# fact-atmega8.net
KiCad netlist of a schematic drawn in EAGLE
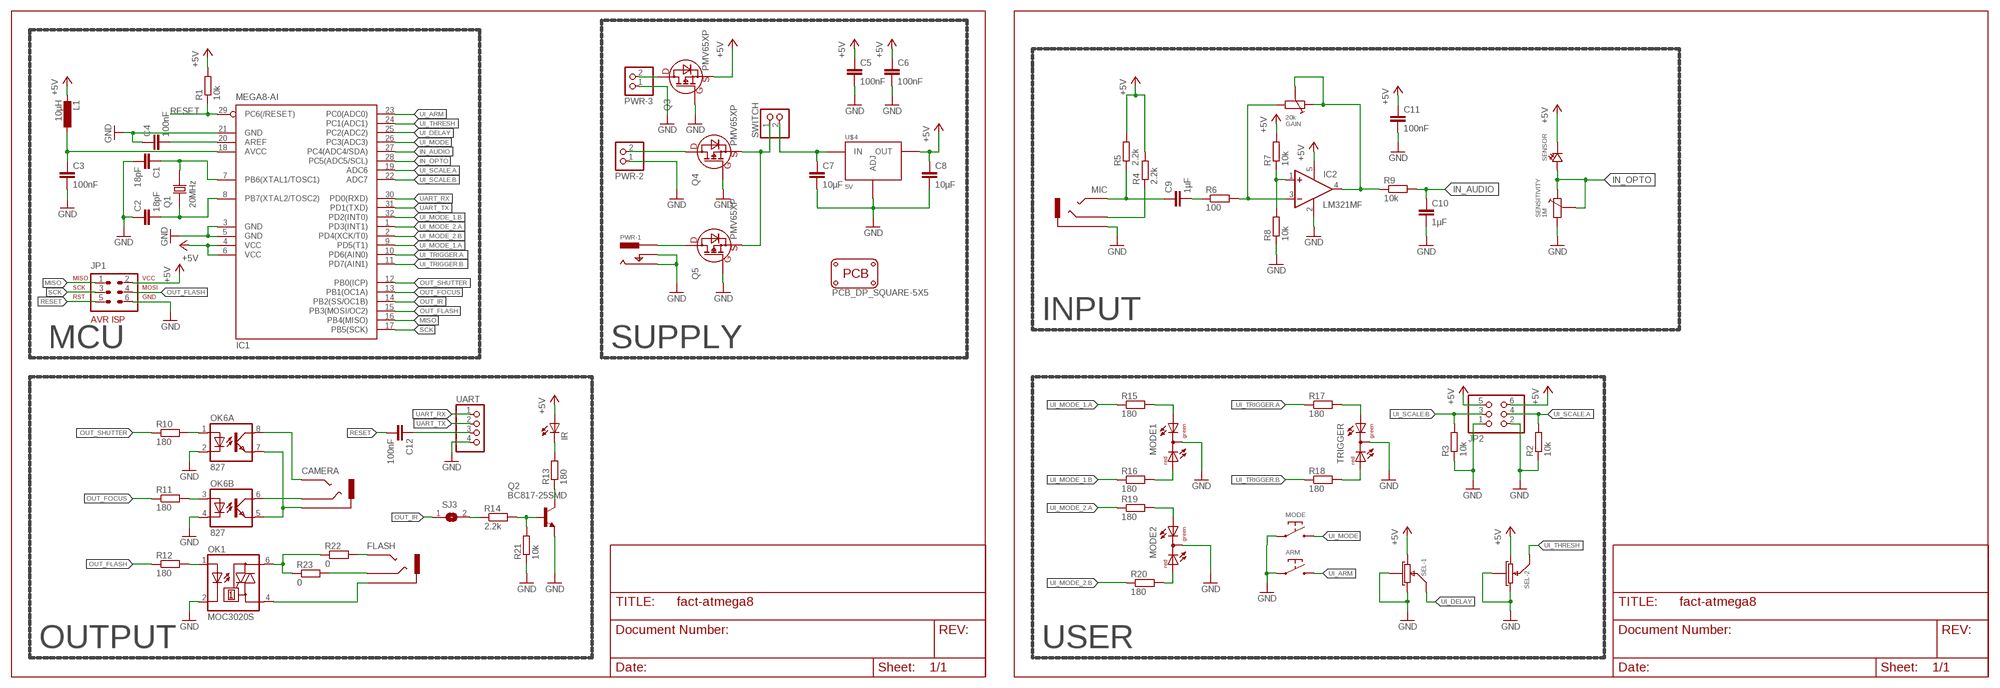
[diagram p0: schematic, sheet 1]

(export (version "E")
  (design (tool "Eeschema 10.0.6"))
  (components
    (comp (ref "ARM")
      (value "SWITCH-DEFAULT_OFF")
      (footprint "eagle-import:SWITCH-GENERIC-4_PIN")
      (libsource (lib "eagle-import") (part "SWITCH-DEFAULT_OFF"))
    )
    (comp (ref "C1")
      (value "18pF")
      (footprint "eagle-import:C0603")
      (libsource (lib "eagle-import") (part "C-EUC0603"))
    )
    (comp (ref "C2")
      (value "18pF")
      (footprint "eagle-import:C0603")
      (libsource (lib "eagle-import") (part "C-EUC0603"))
    )
    (comp (ref "C3")
      (value "100nF")
      (footprint "eagle-import:C0603")
      (libsource (lib "eagle-import") (part "C-EUC0603"))
    )
    (comp (ref "C4")
      (value "100nF")
      (footprint "eagle-import:C0603")
      (libsource (lib "eagle-import") (part "C-EUC0603"))
    )
    (comp (ref "C5")
      (value "100nF")
      (footprint "eagle-import:C0603")
      (libsource (lib "eagle-import") (part "C-EUC0603"))
    )
    (comp (ref "C6")
      (value "100nF")
      (footprint "eagle-import:C0603")
      (libsource (lib "eagle-import") (part "C-EUC0603"))
    )
    (comp (ref "C7")
      (value "10µF")
      (footprint "eagle-import:C0603")
      (libsource (lib "eagle-import") (part "C-EUC0603"))
    )
    (comp (ref "C8")
      (value "10µF")
      (footprint "eagle-import:C0603")
      (libsource (lib "eagle-import") (part "C-EUC0603"))
    )
    (comp (ref "C9")
      (value "1µF")
      (footprint "eagle-import:C0603")
      (libsource (lib "eagle-import") (part "C-EUC0603"))
    )
    (comp (ref "C10")
      (value "1µF")
      (footprint "eagle-import:C0603")
      (libsource (lib "eagle-import") (part "C-EUC0603"))
    )
    (comp (ref "C11")
      (value "100nF")
      (footprint "eagle-import:C0603")
      (libsource (lib "eagle-import") (part "C-EUC0603"))
    )
    (comp (ref "C12")
      (value "100nF")
      (footprint "eagle-import:C0603")
      (libsource (lib "eagle-import") (part "C-EUC0603"))
    )
    (comp (ref "CAMERA")
      (value "AUDIO-STEREO2MM5")
      (footprint "eagle-import:AUDIO-STEREO-2MM5-SJ1-2503A")
      (libsource (lib "eagle-import") (part "AUDIO-STEREO2MM5"))
    )
    (comp (ref "FLASH")
      (value "AUDIO-STEREOCONRAD")
      (footprint "eagle-import:AUDIO-STEREO-CONRAD-KB3-3_PIN")
      (libsource (lib "eagle-import") (part "AUDIO-STEREOCONRAD"))
    )
    (comp (ref "GAIN")
      (value "20k")
      (footprint "eagle-import:TRIM-POT-CA6-VS5")
      (libsource (lib "eagle-import") (part "TRIM-POT"))
    )
    (comp (ref "IC1")
      (value "MEGA8-AI")
      (footprint "eagle-import:TQFP32-08")
      (fields (field (name "MPN") "ATMEGA8-16AU"))
      (libsource (lib "eagle-import") (part "MEGA8-AI"))
    )
    (comp (ref "IC2")
      (value "LM321MF")
      (footprint "eagle-import:SOT23-5")
      (libsource (lib "eagle-import") (part "LM321?MF"))
    )
    (comp (ref "IR")
      (value "LED5MM")
      (footprint "eagle-import:LED5MM")
      (libsource (lib "eagle-import") (part "LED5MM"))
    )
    (comp (ref "JP1")
      (value "AVR-ISP-6VERT")
      (footprint "eagle-import:AVR-ISP-6")
      (libsource (lib "eagle-import") (part "AVR-ISP-6VERT"))
    )
    (comp (ref "JP2")
      (value "PINHD-2X3")
      (footprint "eagle-import:2X03")
      (libsource (lib "eagle-import") (part "PINHD-2X3"))
    )
    (comp (ref "L1")
      (value "10µH")
      (footprint "eagle-import:R0805")
      (libsource (lib "eagle-import") (part "INDUCTOR0805"))
    )
    (comp (ref "MIC")
      (value "AUDIO-STEREOCONRAD-KB3")
      (footprint "eagle-import:AUDIO-STEREO-CONRAD-KB3-3_PIN")
      (libsource (lib "eagle-import") (part "AUDIO-STEREOCONRAD-KB3"))
    )
    (comp (ref "MODE")
      (value "SWITCH-DEFAULT_OFF")
      (footprint "eagle-import:SWITCH-GENERIC-4_PIN")
      (libsource (lib "eagle-import") (part "SWITCH-DEFAULT_OFF"))
    )
    (comp (ref "MODE1")
      (value "DUOLED-RG-C")
      (footprint "eagle-import:DUOLED-C-5MM")
      (libsource (lib "eagle-import") (part "DUOLED-RG-C"))
    )
    (comp (ref "MODE2")
      (value "DUOLED-RG-C")
      (footprint "eagle-import:DUOLED-C-5MM")
      (libsource (lib "eagle-import") (part "DUOLED-RG-C"))
    )
    (comp (ref "OK1")
      (value "MOC3020S")
      (footprint "eagle-import:DIL6-SMD")
      (fields (field (name "MF") "FAIRCHILD SEMICONDUCTOR") (field (name "MPN") "MOC3032S-M"))
      (libsource (lib "eagle-import") (part "MOC30S32"))
    )
    (comp (ref "OK6")
      (value "827")
      (footprint "eagle-import:SMD08")
      (libsource (lib "eagle-import") (part "OPTOCOUPLER-PC827SMD"))
    )
    (comp (ref "PCB1")
      (value "PCB_DP_SQUARE-5X5")
      (footprint "eagle-import:DP5050_V1")
      (libsource (lib "eagle-import") (part "PCB_DP_SQUARE-5X5"))
    )
    (comp (ref "PWR-1")
      (value "POWER-BARREL_JACKPJ-102A")
      (footprint "eagle-import:POWER-BARREL-2MM1-PJ_102A")
      (libsource (lib "eagle-import") (part "POWER-BARREL_JACKPJ-102A"))
    )
    (comp (ref "PWR-2")
      (value "PINHD-1X2")
      (footprint "eagle-import:1X02")
      (libsource (lib "eagle-import") (part "PINHD-1X2"))
    )
    (comp (ref "PWR-3")
      (value "PINHD-1X2")
      (footprint "eagle-import:1X02")
      (libsource (lib "eagle-import") (part "PINHD-1X2"))
    )
    (comp (ref "Q1")
      (value "20MHz")
      (footprint "eagle-import:CRYSTAL-SMD-5MM_X_3.2MM")
      (libsource (lib "eagle-import") (part "CRYSTAL"))
    )
    (comp (ref "Q2")
      (value "BC817-25SMD")
      (footprint "eagle-import:SOT23-BEC")
      (libsource (lib "eagle-import") (part "BC817SMD-25"))
    )
    (comp (ref "Q3")
      (value "PMV65XP")
      (footprint "eagle-import:SOT23")
      (libsource (lib "eagle-import") (part "FET-P"))
    )
    (comp (ref "Q4")
      (value "PMV65XP")
      (footprint "eagle-import:SOT23")
      (libsource (lib "eagle-import") (part "FET-P"))
    )
    (comp (ref "Q5")
      (value "PMV65XP")
      (footprint "eagle-import:SOT23")
      (libsource (lib "eagle-import") (part "FET-P"))
    )
    (comp (ref "R1")
      (value "10k")
      (footprint "eagle-import:R0603")
      (libsource (lib "eagle-import") (part "R-EU_R0603"))
    )
    (comp (ref "R2")
      (value "10k")
      (footprint "eagle-import:R0603")
      (libsource (lib "eagle-import") (part "R-EU_R0603"))
    )
    (comp (ref "R3")
      (value "10k")
      (footprint "eagle-import:R0603")
      (libsource (lib "eagle-import") (part "R-EU_R0603"))
    )
    (comp (ref "R4")
      (value "2.2k")
      (footprint "eagle-import:R0603")
      (libsource (lib "eagle-import") (part "R-EU_R0603"))
    )
    (comp (ref "R5")
      (value "2.2k")
      (footprint "eagle-import:R0603")
      (libsource (lib "eagle-import") (part "R-EU_R0603"))
    )
    (comp (ref "R6")
      (value "100")
      (footprint "eagle-import:R0603")
      (libsource (lib "eagle-import") (part "R-EU_R0603"))
    )
    (comp (ref "R7")
      (value "10k")
      (footprint "eagle-import:R0603")
      (libsource (lib "eagle-import") (part "R-EU_R0603"))
    )
    (comp (ref "R8")
      (value "10k")
      (footprint "eagle-import:R0603")
      (libsource (lib "eagle-import") (part "R-EU_R0603"))
    )
    (comp (ref "R9")
      (value "10k")
      (footprint "eagle-import:R0603")
      (libsource (lib "eagle-import") (part "R-EU_R0603"))
    )
    (comp (ref "R10")
      (value "180")
      (footprint "eagle-import:R0603")
      (libsource (lib "eagle-import") (part "R-EU_R0603"))
    )
    (comp (ref "R11")
      (value "180")
      (footprint "eagle-import:R0603")
      (libsource (lib "eagle-import") (part "R-EU_R0603"))
    )
    (comp (ref "R12")
      (value "180")
      (footprint "eagle-import:R0603")
      (libsource (lib "eagle-import") (part "R-EU_R0603"))
    )
    (comp (ref "R13")
      (value "180")
      (footprint "eagle-import:R0603")
      (libsource (lib "eagle-import") (part "R-EU_R0603"))
    )
    (comp (ref "R14")
      (value "2.2k")
      (footprint "eagle-import:R0603")
      (libsource (lib "eagle-import") (part "R-EU_R0603"))
    )
    (comp (ref "R15")
      (value "180")
      (footprint "eagle-import:R0603")
      (libsource (lib "eagle-import") (part "R-EU_R0603"))
    )
    (comp (ref "R16")
      (value "180")
      (footprint "eagle-import:R0603")
      (libsource (lib "eagle-import") (part "R-EU_R0603"))
    )
    (comp (ref "R17")
      (value "180")
      (footprint "eagle-import:R0603")
      (libsource (lib "eagle-import") (part "R-EU_R0603"))
    )
    (comp (ref "R18")
      (value "180")
      (footprint "eagle-import:R0603")
      (libsource (lib "eagle-import") (part "R-EU_R0603"))
    )
    (comp (ref "R19")
      (value "180")
      (footprint "eagle-import:R0603")
      (libsource (lib "eagle-import") (part "R-EU_R0603"))
    )
    (comp (ref "R20")
      (value "180")
      (footprint "eagle-import:R0603")
      (libsource (lib "eagle-import") (part "R-EU_R0603"))
    )
    (comp (ref "R21")
      (value "10k")
      (footprint "eagle-import:R0603")
      (libsource (lib "eagle-import") (part "R-EU_R0603"))
    )
    (comp (ref "R22")
      (value "0")
      (footprint "eagle-import:R1206")
      (libsource (lib "eagle-import") (part "rcl_R-EU_R1206"))
    )
    (comp (ref "R23")
      (value "0")
      (footprint "eagle-import:R1206")
      (libsource (lib "eagle-import") (part "rcl_R-EU_R1206"))
    )
    (comp (ref "SEL")
      (value "DUAL-POT")
      (footprint "eagle-import:POT-DUAL-P090")
      (libsource (lib "eagle-import") (part "DUAL-POT"))
    )
    (comp (ref "SENSITIVITY")
      (value "1M")
      (footprint "eagle-import:TRIM-POT-CA6-VS5")
      (libsource (lib "eagle-import") (part "TRIM-POT"))
    )
    (comp (ref "SENSOR")
      (value "PHOTODIODE")
      (footprint "eagle-import:LED-5MM")
      (libsource (lib "eagle-import") (part "PHOTODIODE"))
    )
    (comp (ref "SJ3") (value "SJ") (footprint "eagle-import:SJ") (libsource (lib "eagle-import") (part "SJ")))
    (comp (ref "SWITCH")
      (value "PINHD-1X2")
      (footprint "eagle-import:1X02")
      (libsource (lib "eagle-import") (part "PINHD-1X2"))
    )
    (comp (ref "TRIGGER")
      (value "DUOLED-RG-C")
      (footprint "eagle-import:DUOLED-C-5MM")
      (libsource (lib "eagle-import") (part "DUOLED-RG-C"))
    )
    (comp (ref "U$4")
      (value "5V")
      (footprint "eagle-import:SOT223")
      (libsource (lib "eagle-import") (part "REGULATOR-TLV1117SOT223"))
    )
    (comp (ref "UART")
      (value "PINHD-1X4")
      (footprint "eagle-import:1X04")
      (libsource (lib "eagle-import") (part "PINHD-1X4"))
    )
  )
  (nets
    (net (code "1") (name "+5V") (class "Default")
      (node (ref "C11") (pin "1") (pinfunction "1_1") (pintype "passive"))
      (node (ref "C5") (pin "1") (pinfunction "1_1") (pintype "passive"))
      (node (ref "C6") (pin "1") (pinfunction "1_1") (pintype "passive"))
      (node (ref "C8") (pin "1") (pinfunction "1_1") (pintype "passive"))
      (node (ref "IC1") (pin "4") (pinfunction "VCC_4") (pintype "power_in"))
      (node (ref "IC1") (pin "6") (pinfunction "VCC_6") (pintype "power_in"))
      (node (ref "IC2") (pin "5") (pinfunction "V+_5") (pintype "power_in"))
      (node (ref "IR") (pin "A") (pinfunction "A_A") (pintype "passive"))
      (node (ref "JP1") (pin "2") (pinfunction "2_2") (pintype "passive"))
      (node (ref "JP2") (pin "5") (pinfunction "5_5") (pintype "passive"))
      (node (ref "JP2") (pin "6") (pinfunction "6_6") (pintype "passive"))
      (node (ref "L1") (pin "2") (pinfunction "2_2") (pintype "passive"))
      (node (ref "Q3") (pin "P$2") (pinfunction "SOURCE_P$2") (pintype "bidirectional"))
      (node (ref "R1") (pin "2") (pinfunction "2_2") (pintype "passive"))
      (node (ref "R4") (pin "2") (pinfunction "2_2") (pintype "passive"))
      (node (ref "R5") (pin "2") (pinfunction "2_2") (pintype "passive"))
      (node (ref "R7") (pin "2") (pinfunction "2_2") (pintype "passive"))
      (node (ref "SEL") (pin "P1-3") (pinfunction "B_P1-3") (pintype "bidirectional"))
      (node (ref "SEL") (pin "P2-1") (pinfunction "A_P2-1") (pintype "bidirectional"))
      (node (ref "SENSOR") (pin "K") (pinfunction "C_K") (pintype "bidirectional"))
      (node (ref "U$4") (pin "2") (pinfunction "OUT_2") (pintype "bidirectional"))
    )
    (net (code "2") (name "GND") (class "Default")
      (node (ref "ARM") (pin "P$1") (pinfunction "P$1_P$1") (pintype "bidirectional"))
      (node (ref "ARM") (pin "P$2") (pinfunction "P$1_P$2") (pintype "bidirectional"))
      (node (ref "C1") (pin "2") (pinfunction "2_2") (pintype "passive"))
      (node (ref "C10") (pin "2") (pinfunction "2_2") (pintype "passive"))
      (node (ref "C11") (pin "2") (pinfunction "2_2") (pintype "passive"))
      (node (ref "C2") (pin "1") (pinfunction "1_1") (pintype "passive"))
      (node (ref "C3") (pin "2") (pinfunction "2_2") (pintype "passive"))
      (node (ref "C4") (pin "1") (pinfunction "1_1") (pintype "passive"))
      (node (ref "C5") (pin "2") (pinfunction "2_2") (pintype "passive"))
      (node (ref "C6") (pin "2") (pinfunction "2_2") (pintype "passive"))
      (node (ref "C7") (pin "2") (pinfunction "2_2") (pintype "passive"))
      (node (ref "C8") (pin "2") (pinfunction "2_2") (pintype "passive"))
      (node (ref "IC1") (pin "21") (pinfunction "GND_21") (pintype "power_in"))
      (node (ref "IC1") (pin "3") (pinfunction "GND_3") (pintype "power_in"))
      (node (ref "IC1") (pin "5") (pinfunction "GND_5") (pintype "power_in"))
      (node (ref "IC2") (pin "2") (pinfunction "V-_2") (pintype "power_in"))
      (node (ref "JP1") (pin "6") (pinfunction "6_6") (pintype "passive"))
      (node (ref "JP2") (pin "1") (pinfunction "1_1") (pintype "passive"))
      (node (ref "JP2") (pin "2") (pinfunction "2_2") (pintype "passive"))
      (node (ref "MIC") (pin "2.1") (pinfunction "SLEEVE_2.1") (pintype "passive"))
      (node (ref "MIC") (pin "2.2") (pinfunction "SLEEVE_2.2") (pintype "passive"))
      (node (ref "MODE") (pin "P$1") (pinfunction "P$1_P$1") (pintype "bidirectional"))
      (node (ref "MODE") (pin "P$2") (pinfunction "P$1_P$2") (pintype "bidirectional"))
      (node (ref "MODE1") (pin "C") (pinfunction "C_C") (pintype "passive"))
      (node (ref "MODE2") (pin "C") (pinfunction "C_C") (pintype "passive"))
      (node (ref "OK1") (pin "2") (pinfunction "C_2") (pintype "passive"))
      (node (ref "OK6") (pin "2") (pinfunction "C_2") (pintype "passive"))
      (node (ref "OK6") (pin "4") (pinfunction "C_4") (pintype "passive"))
      (node (ref "PWR-1") (pin "P$2") (pinfunction "OUTER_P$2") (pintype "bidirectional"))
      (node (ref "PWR-1") (pin "P$3") (pinfunction "SWITCH_P$3") (pintype "bidirectional"))
      (node (ref "PWR-2") (pin "1") (pinfunction "1_1") (pintype "passive"))
      (node (ref "PWR-3") (pin "1") (pinfunction "1_1") (pintype "passive"))
      (node (ref "Q2") (pin "E") (pinfunction "E_E") (pintype "passive"))
      (node (ref "Q3") (pin "P$1") (pinfunction "GATE_P$1") (pintype "bidirectional"))
      (node (ref "Q4") (pin "P$1") (pinfunction "GATE_P$1") (pintype "bidirectional"))
      (node (ref "Q5") (pin "P$1") (pinfunction "GATE_P$1") (pintype "bidirectional"))
      (node (ref "R2") (pin "1") (pinfunction "1_1") (pintype "passive"))
      (node (ref "R21") (pin "1") (pinfunction "1_1") (pintype "passive"))
      (node (ref "R3") (pin "1") (pinfunction "1_1") (pintype "passive"))
      (node (ref "R8") (pin "1") (pinfunction "1_1") (pintype "passive"))
      (node (ref "SEL") (pin "CENTER") (pinfunction "SHIELD_CENTER") (pintype "bidirectional"))
      (node (ref "SEL") (pin "G1-S") (pinfunction "SHIELD_G1-S") (pintype "bidirectional"))
      (node (ref "SEL") (pin "G2-S") (pinfunction "SHIELD_G2-S") (pintype "bidirectional"))
      (node (ref "SEL") (pin "P1-1") (pinfunction "A_P1-1") (pintype "bidirectional"))
      (node (ref "SEL") (pin "P2-3") (pinfunction "B_P2-3") (pintype "bidirectional"))
      (node (ref "SENSITIVITY") (pin "P$2") (pinfunction "P$2_P$2") (pintype "bidirectional"))
      (node (ref "TRIGGER") (pin "C") (pinfunction "C_C") (pintype "passive"))
      (node (ref "U$4") (pin "1") (pinfunction "ADJ_1") (pintype "bidirectional"))
      (node (ref "U$4") (pin "4") (pinfunction "ADJ_4") (pintype "bidirectional"))
      (node (ref "UART") (pin "4") (pinfunction "4_4") (pintype "passive"))
    )
    (net (code "3") (name "IN_AUDIO") (class "Default")
      (node (ref "C10") (pin "1") (pinfunction "1_1") (pintype "passive"))
      (node (ref "IC1") (pin "27") (pinfunction "PC4(ADC4/SDA)_27") (pintype "bidirectional"))
      (node (ref "R9") (pin "2") (pinfunction "2_2") (pintype "passive"))
    )
    (net (code "4") (name "IN_OPTO") (class "Default")
      (node (ref "IC1") (pin "28") (pinfunction "PC5(ADC5/SCL)_28") (pintype "bidirectional"))
      (node (ref "SENSITIVITY") (pin "CENTER") (pinfunction "CENTER_CENTER") (pintype "bidirectional"))
      (node (ref "SENSITIVITY") (pin "P$1") (pinfunction "P$1_P$1") (pintype "bidirectional"))
      (node (ref "SENSOR") (pin "A") (pinfunction "A_A") (pintype "bidirectional"))
    )
    (net (code "5") (name "MISO") (class "Default")
      (node (ref "IC1") (pin "16") (pinfunction "PB4(MISO)_16") (pintype "bidirectional"))
      (node (ref "JP1") (pin "1") (pinfunction "1_1") (pintype "passive"))
    )
    (net (code "6") (name "Net-(C9-Pad2)") (class "Default")
      (node (ref "C9") (pin "2") (pinfunction "2_2") (pintype "passive"))
      (node (ref "R6") (pin "1") (pinfunction "1_1") (pintype "passive"))
    )
    (net (code "7") (name "Net-(C12-Pad1)") (class "Default")
      (node (ref "C12") (pin "1") (pinfunction "1_1") (pintype "passive"))
      (node (ref "UART") (pin "3") (pinfunction "3_3") (pintype "passive"))
    )
    (net (code "8") (name "Net-(CAMERA-RING)") (class "Default")
      (node (ref "CAMERA") (pin "P$4") (pinfunction "RING_P$4") (pintype "passive"))
      (node (ref "OK6") (pin "6") (pinfunction "COL_6") (pintype "passive"))
    )
    (net (code "9") (name "Net-(CAMERA-SLEEVE)") (class "Default")
      (node (ref "CAMERA") (pin "P$1") (pinfunction "SLEEVE_P$1") (pintype "passive"))
      (node (ref "OK6") (pin "5") (pinfunction "EMIT_5") (pintype "passive"))
      (node (ref "OK6") (pin "7") (pinfunction "EMIT_7") (pintype "passive"))
    )
    (net (code "10") (name "Net-(FLASH-RING-Pad2.1)") (class "Default")
      (node (ref "FLASH") (pin "2.1") (pinfunction "RING_2.1") (pintype "passive"))
      (node (ref "FLASH") (pin "2.2") (pinfunction "RING_2.2") (pintype "passive"))
      (node (ref "R23") (pin "2") (pinfunction "2_2") (pintype "passive"))
    )
    (net (code "11") (name "Net-(FLASH-SLEEVE)") (class "Default")
      (node (ref "FLASH") (pin "1") (pinfunction "SLEEVE_1") (pintype "passive"))
      (node (ref "OK1") (pin "4") (pinfunction "A1_4") (pintype "passive"))
    )
    (net (code "12") (name "Net-(FLASH-TIP)") (class "Default")
      (node (ref "FLASH") (pin "3") (pinfunction "TIP_3") (pintype "passive"))
      (node (ref "R22") (pin "2") (pinfunction "2_2") (pintype "passive"))
    )
    (net (code "13") (name "Net-(IC1-AREF)") (class "Default")
      (node (ref "C4") (pin "2") (pinfunction "2_2") (pintype "passive"))
      (node (ref "IC1") (pin "20") (pinfunction "AREF_20") (pintype "passive"))
    )
    (net (code "14") (name "Net-(IC1-AVCC)") (class "Default")
      (node (ref "C3") (pin "1") (pinfunction "1_1") (pintype "passive"))
      (node (ref "IC1") (pin "18") (pinfunction "AVCC_18") (pintype "power_in"))
      (node (ref "L1") (pin "1") (pinfunction "1_1") (pintype "passive"))
    )
    (net (code "15") (name "Net-(IC1-PB6(XTAL1{slash}TOSC1))") (class "Default")
      (node (ref "C1") (pin "1") (pinfunction "1_1") (pintype "passive"))
      (node (ref "IC1") (pin "7") (pinfunction "PB6(XTAL1/TOSC1)_7") (pintype "bidirectional"))
      (node (ref "Q1") (pin "P$2") (pinfunction "C2_P$2") (pintype "passive"))
    )
    (net (code "16") (name "Net-(IC1-PB7(XTAL2{slash}TOSC2))") (class "Default")
      (node (ref "C2") (pin "2") (pinfunction "2_2") (pintype "passive"))
      (node (ref "IC1") (pin "8") (pinfunction "PB7(XTAL2/TOSC2)_8") (pintype "bidirectional"))
      (node (ref "Q1") (pin "P$1") (pinfunction "C1_P$1") (pintype "passive"))
    )
    (net (code "17") (name "Net-(IC2-+IN)") (class "Default")
      (node (ref "IC2") (pin "1") (pinfunction "+IN_1") (pintype "input"))
      (node (ref "R7") (pin "1") (pinfunction "1_1") (pintype "passive"))
      (node (ref "R8") (pin "2") (pinfunction "2_2") (pintype "passive"))
    )
    (net (code "18") (name "Net-(IC2--IN)") (class "Default")
      (node (ref "GAIN") (pin "P$2") (pinfunction "P$2_P$2") (pintype "bidirectional"))
      (node (ref "IC2") (pin "3") (pinfunction "-IN_3") (pintype "input"))
      (node (ref "R6") (pin "2") (pinfunction "2_2") (pintype "passive"))
    )
    (net (code "19") (name "Net-(IC2-OUT)") (class "Default")
      (node (ref "GAIN") (pin "CENTER") (pinfunction "CENTER_CENTER") (pintype "bidirectional"))
      (node (ref "GAIN") (pin "P$1") (pinfunction "P$1_P$1") (pintype "bidirectional"))
      (node (ref "IC2") (pin "4") (pinfunction "OUT_4") (pintype "output"))
      (node (ref "R9") (pin "1") (pinfunction "1_1") (pintype "passive"))
    )
    (net (code "20") (name "Net-(IR-C)") (class "Default")
      (node (ref "IR") (pin "K") (pinfunction "C_K") (pintype "passive"))
      (node (ref "R13") (pin "2") (pinfunction "2_2") (pintype "passive"))
    )
    (net (code "21") (name "Net-(MIC-RING)") (class "Default")
      (node (ref "MIC") (pin "1") (pinfunction "RING_1") (pintype "passive"))
      (node (ref "R4") (pin "1") (pinfunction "1_1") (pintype "passive"))
    )
    (net (code "22") (name "Net-(MIC-TIP)") (class "Default")
      (node (ref "C9") (pin "1") (pinfunction "1_1") (pintype "passive"))
      (node (ref "MIC") (pin "3") (pinfunction "TIP_3") (pintype "passive"))
      (node (ref "R5") (pin "1") (pinfunction "1_1") (pintype "passive"))
    )
    (net (code "23") (name "Net-(MODE1-AG)") (class "Default")
      (node (ref "MODE1") (pin "AX") (pinfunction "AG_AX") (pintype "passive"))
      (node (ref "R15") (pin "2") (pinfunction "2_2") (pintype "passive"))
    )
    (net (code "24") (name "Net-(MODE1-PadAR)") (class "Default")
      (node (ref "MODE1") (pin "AR") (pinfunction "AR_AR") (pintype "passive"))
      (node (ref "R16") (pin "2") (pinfunction "2_2") (pintype "passive"))
    )
    (net (code "25") (name "Net-(MODE2-AG)") (class "Default")
      (node (ref "MODE2") (pin "AX") (pinfunction "AG_AX") (pintype "passive"))
      (node (ref "R19") (pin "2") (pinfunction "2_2") (pintype "passive"))
    )
    (net (code "26") (name "Net-(MODE2-PadAR)") (class "Default")
      (node (ref "MODE2") (pin "AR") (pinfunction "AR_AR") (pintype "passive"))
      (node (ref "R20") (pin "2") (pinfunction "2_2") (pintype "passive"))
    )
    (net (code "27") (name "Net-(OK1-A)") (class "Default")
      (node (ref "OK1") (pin "1") (pinfunction "A_1") (pintype "passive"))
      (node (ref "R12") (pin "2") (pinfunction "2_2") (pintype "passive"))
    )
    (net (code "28") (name "Net-(OK1-A2)") (class "Default")
      (node (ref "OK1") (pin "6") (pinfunction "A2_6") (pintype "passive"))
      (node (ref "R22") (pin "1") (pinfunction "1_1") (pintype "passive"))
      (node (ref "R23") (pin "1") (pinfunction "1_1") (pintype "passive"))
    )
    (net (code "29") (name "Net-(OK6A-A)") (class "Default")
      (node (ref "OK6") (pin "1") (pinfunction "A_1") (pintype "passive"))
      (node (ref "R10") (pin "2") (pinfunction "2_2") (pintype "passive"))
    )
    (net (code "30") (name "Net-(OK6A-COL)") (class "Default")
      (node (ref "CAMERA") (pin "P$2") (pinfunction "TIP_P$2") (pintype "passive"))
      (node (ref "CAMERA") (pin "P$3") (pinfunction "TIP_P$3") (pintype "passive"))
      (node (ref "OK6") (pin "8") (pinfunction "COL_8") (pintype "passive"))
    )
    (net (code "31") (name "Net-(OK6B-A)") (class "Default")
      (node (ref "OK6") (pin "3") (pinfunction "A_3") (pintype "passive"))
      (node (ref "R11") (pin "2") (pinfunction "2_2") (pintype "passive"))
    )
    (net (code "32") (name "Net-(PWR-1-CENTER)") (class "Default")
      (node (ref "PWR-1") (pin "P$1") (pinfunction "CENTER_P$1") (pintype "bidirectional"))
      (node (ref "Q5") (pin "P$3") (pinfunction "DRAIN_P$3") (pintype "bidirectional"))
    )
    (net (code "33") (name "Net-(Q2-PadB)") (class "Default")
      (node (ref "Q2") (pin "B") (pinfunction "B_B") (pintype "passive"))
      (node (ref "R14") (pin "2") (pinfunction "2_2") (pintype "passive"))
      (node (ref "R21") (pin "2") (pinfunction "2_2") (pintype "passive"))
    )
    (net (code "34") (name "Net-(Q2-PadC)") (class "Default")
      (node (ref "Q2") (pin "C") (pinfunction "C_C") (pintype "passive"))
      (node (ref "R13") (pin "1") (pinfunction "1_1") (pintype "passive"))
    )
    (net (code "35") (name "Net-(Q3-DRAIN)") (class "Default")
      (node (ref "PWR-3") (pin "2") (pinfunction "2_2") (pintype "passive"))
      (node (ref "Q3") (pin "P$3") (pinfunction "DRAIN_P$3") (pintype "bidirectional"))
    )
    (net (code "36") (name "Net-(Q4-DRAIN)") (class "Default")
      (node (ref "PWR-2") (pin "2") (pinfunction "2_2") (pintype "passive"))
      (node (ref "Q4") (pin "P$3") (pinfunction "DRAIN_P$3") (pintype "bidirectional"))
    )
    (net (code "37") (name "Net-(Q4-SOURCE)") (class "Default")
      (node (ref "Q4") (pin "P$2") (pinfunction "SOURCE_P$2") (pintype "bidirectional"))
      (node (ref "Q5") (pin "P$2") (pinfunction "SOURCE_P$2") (pintype "bidirectional"))
      (node (ref "SWITCH") (pin "1") (pinfunction "1_1") (pintype "passive"))
    )
    (net (code "38") (name "Net-(R14-Pad1)") (class "Default")
      (node (ref "R14") (pin "1") (pinfunction "1_1") (pintype "passive"))
      (node (ref "SJ3") (pin "2") (pinfunction "2_2") (pintype "passive"))
    )
    (net (code "39") (name "Net-(R18-Pad2)") (class "Default")
      (node (ref "R18") (pin "2") (pinfunction "2_2") (pintype "passive"))
      (node (ref "TRIGGER") (pin "AR") (pinfunction "AR_AR") (pintype "passive"))
    )
    (net (code "40") (name "Net-(TRIGGER-AG)") (class "Default")
      (node (ref "R17") (pin "2") (pinfunction "2_2") (pintype "passive"))
      (node (ref "TRIGGER") (pin "AX") (pinfunction "AG_AX") (pintype "passive"))
    )
    (net (code "41") (name "Net-(U$4-IN)") (class "Default")
      (node (ref "C7") (pin "1") (pinfunction "1_1") (pintype "passive"))
      (node (ref "SWITCH") (pin "2") (pinfunction "2_2") (pintype "passive"))
      (node (ref "U$4") (pin "3") (pinfunction "IN_3") (pintype "bidirectional"))
    )
    (net (code "42") (name "OUT_FLASH") (class "Default")
      (node (ref "IC1") (pin "15") (pinfunction "PB3(MOSI/OC2)_15") (pintype "bidirectional"))
      (node (ref "JP1") (pin "4") (pinfunction "4_4") (pintype "passive"))
      (node (ref "R12") (pin "1") (pinfunction "1_1") (pintype "passive"))
    )
    (net (code "43") (name "OUT_FOCUS") (class "Default")
      (node (ref "IC1") (pin "13") (pinfunction "PB1(OC1A)_13") (pintype "bidirectional"))
      (node (ref "R11") (pin "1") (pinfunction "1_1") (pintype "passive"))
    )
    (net (code "44") (name "OUT_IR") (class "Default")
      (node (ref "IC1") (pin "14") (pinfunction "PB2(SS/OC1B)_14") (pintype "bidirectional"))
      (node (ref "SJ3") (pin "1") (pinfunction "1_1") (pintype "passive"))
    )
    (net (code "45") (name "OUT_SHUTTER") (class "Default")
      (node (ref "IC1") (pin "12") (pinfunction "PB0(ICP)_12") (pintype "bidirectional"))
      (node (ref "R10") (pin "1") (pinfunction "1_1") (pintype "passive"))
    )
    (net (code "46") (name "RESET") (class "Default")
      (node (ref "C12") (pin "2") (pinfunction "2_2") (pintype "passive"))
      (node (ref "IC1") (pin "29") (pinfunction "PC6(/RESET)_29") (pintype "bidirectional"))
      (node (ref "JP1") (pin "5") (pinfunction "5_5") (pintype "passive"))
      (node (ref "R1") (pin "1") (pinfunction "1_1") (pintype "passive"))
    )
    (net (code "47") (name "SCK") (class "Default")
      (node (ref "IC1") (pin "17") (pinfunction "PB5(SCK)_17") (pintype "bidirectional"))
      (node (ref "JP1") (pin "3") (pinfunction "3_3") (pintype "passive"))
    )
    (net (code "48") (name "UART_RX") (class "Default")
      (node (ref "IC1") (pin "30") (pinfunction "PD0(RXD)_30") (pintype "bidirectional"))
      (node (ref "UART") (pin "1") (pinfunction "1_1") (pintype "passive"))
    )
    (net (code "49") (name "UART_TX") (class "Default")
      (node (ref "IC1") (pin "31") (pinfunction "PD1(TXD)_31") (pintype "bidirectional"))
      (node (ref "UART") (pin "2") (pinfunction "2_2") (pintype "passive"))
    )
    (net (code "50") (name "UI_ARM") (class "Default")
      (node (ref "ARM") (pin "P$3") (pinfunction "P$2_P$3") (pintype "bidirectional"))
      (node (ref "ARM") (pin "P$4") (pinfunction "P$2_P$4") (pintype "bidirectional"))
      (node (ref "IC1") (pin "23") (pinfunction "PC0(ADC0)_23") (pintype "bidirectional"))
    )
    (net (code "51") (name "UI_DELAY") (class "Default")
      (node (ref "IC1") (pin "25") (pinfunction "PC2(ADC2)_25") (pintype "bidirectional"))
      (node (ref "SEL") (pin "P1-2") (pinfunction "M_P1-2") (pintype "bidirectional"))
    )
    (net (code "52") (name "UI_MODE") (class "Default")
      (node (ref "IC1") (pin "26") (pinfunction "PC3(ADC3)_26") (pintype "bidirectional"))
      (node (ref "MODE") (pin "P$3") (pinfunction "P$2_P$3") (pintype "bidirectional"))
      (node (ref "MODE") (pin "P$4") (pinfunction "P$2_P$4") (pintype "bidirectional"))
    )
    (net (code "53") (name "UI_MODE_1.A") (class "Default")
      (node (ref "IC1") (pin "9") (pinfunction "PD5(T1)_9") (pintype "bidirectional"))
      (node (ref "R15") (pin "1") (pinfunction "1_1") (pintype "passive"))
    )
    (net (code "54") (name "UI_MODE_1.B") (class "Default")
      (node (ref "IC1") (pin "32") (pinfunction "PD2(INT0)_32") (pintype "bidirectional"))
      (node (ref "R16") (pin "1") (pinfunction "1_1") (pintype "passive"))
    )
    (net (code "55") (name "UI_MODE_2.A") (class "Default")
      (node (ref "IC1") (pin "1") (pinfunction "PD3(INT1)_1") (pintype "bidirectional"))
      (node (ref "R19") (pin "1") (pinfunction "1_1") (pintype "passive"))
    )
    (net (code "56") (name "UI_MODE_2.B") (class "Default")
      (node (ref "IC1") (pin "2") (pinfunction "PD4(XCK/T0)_2") (pintype "bidirectional"))
      (node (ref "R20") (pin "1") (pinfunction "1_1") (pintype "passive"))
    )
    (net (code "57") (name "UI_SCALE.A") (class "Default")
      (node (ref "IC1") (pin "19") (pinfunction "ADC6_19") (pintype "bidirectional"))
      (node (ref "JP2") (pin "4") (pinfunction "4_4") (pintype "passive"))
      (node (ref "R2") (pin "2") (pinfunction "2_2") (pintype "passive"))
    )
    (net (code "58") (name "UI_SCALE.B") (class "Default")
      (node (ref "IC1") (pin "22") (pinfunction "ADC7_22") (pintype "bidirectional"))
      (node (ref "JP2") (pin "3") (pinfunction "3_3") (pintype "passive"))
      (node (ref "R3") (pin "2") (pinfunction "2_2") (pintype "passive"))
    )
    (net (code "59") (name "UI_THRESH") (class "Default")
      (node (ref "IC1") (pin "24") (pinfunction "PC1(ADC1)_24") (pintype "bidirectional"))
      (node (ref "SEL") (pin "P2-2") (pinfunction "M_P2-2") (pintype "bidirectional"))
    )
    (net (code "60") (name "UI_TRIGGER.A") (class "Default")
      (node (ref "IC1") (pin "10") (pinfunction "PD6(AIN0)_10") (pintype "bidirectional"))
      (node (ref "R17") (pin "1") (pinfunction "1_1") (pintype "passive"))
    )
    (net (code "61") (name "UI_TRIGGER.B") (class "Default")
      (node (ref "IC1") (pin "11") (pinfunction "PD7(AIN1)_11") (pintype "bidirectional"))
      (node (ref "R18") (pin "1") (pinfunction "1_1") (pintype "passive"))
    )
  )
)
